# ProPrj_OPA4377__2025-12-12.net
KiCad netlist of a schematic drawn in EasyEDA Pro
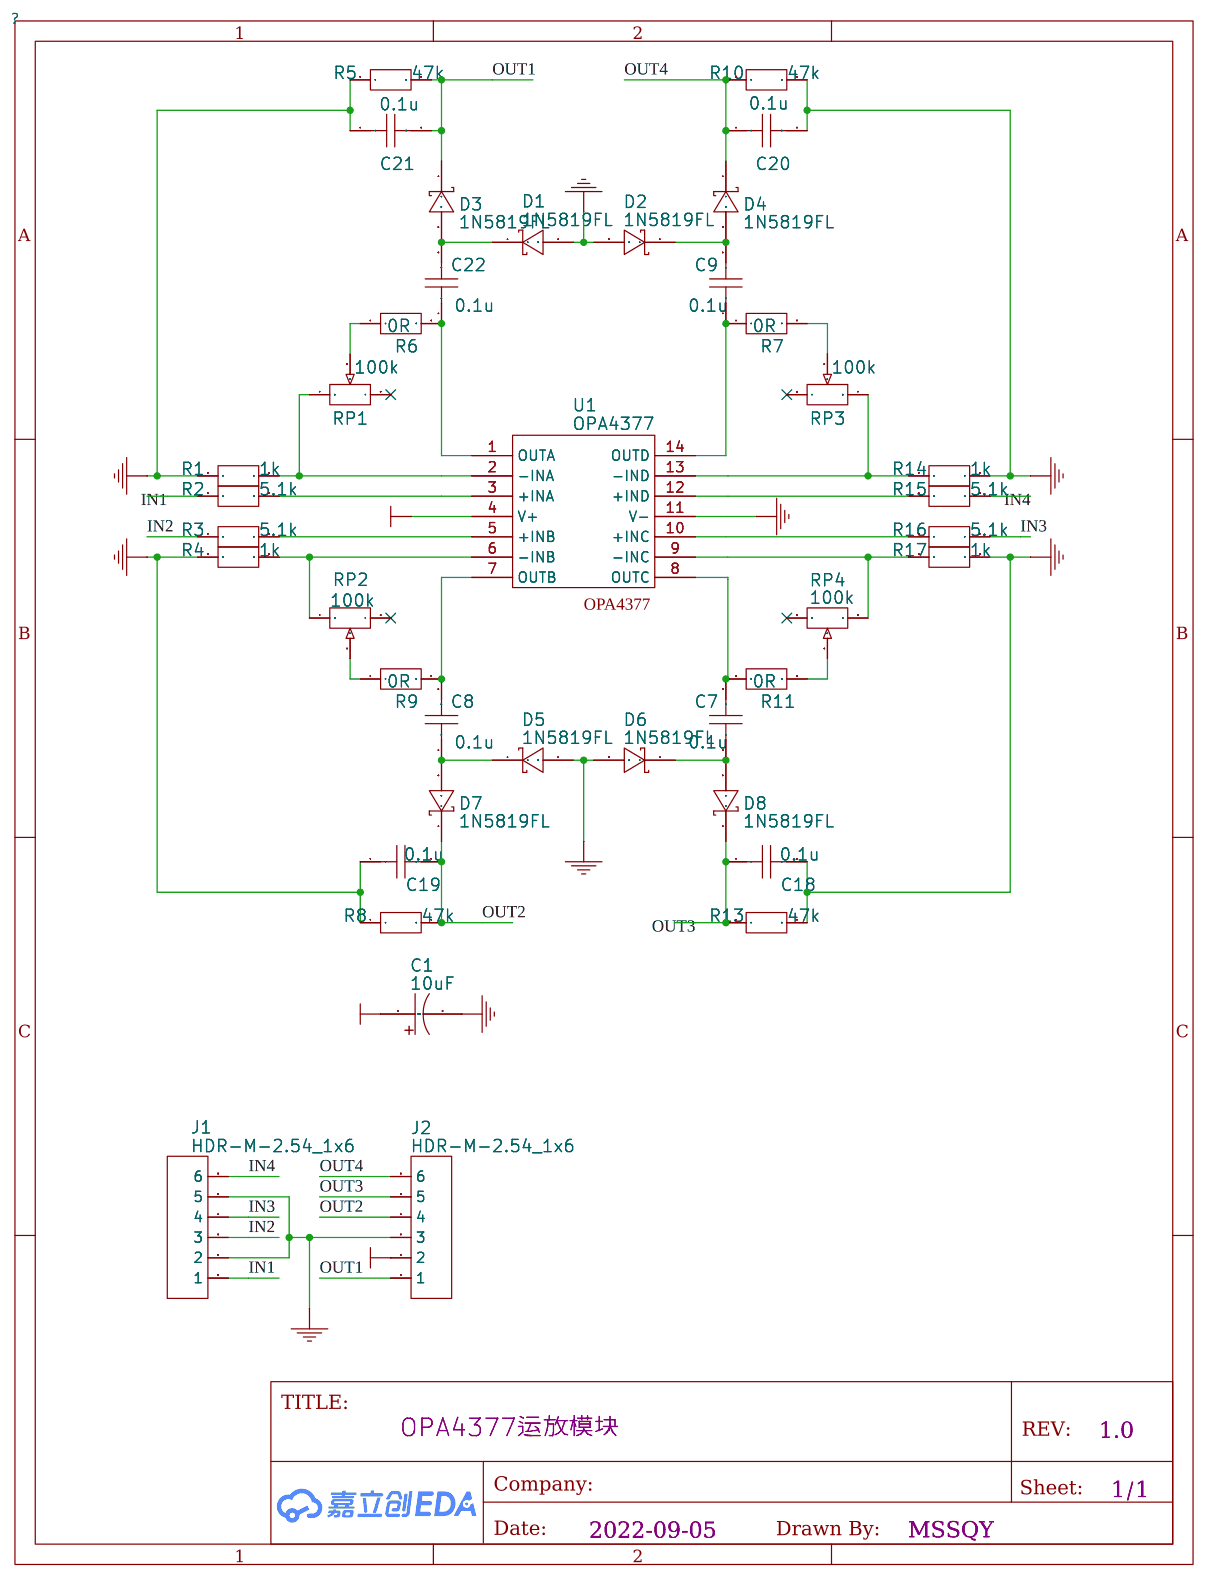
[diagram p0: schematic sheet]

(export (version "E")
  (design (tool "Eeschema 10.0.6"))
  (components
    (comp (ref "C1")
      (value "10uF")
      (fields (field (name "Manufacturer Part") "CA45-A-10V-10μF-K") (field (name "Manufacturer") "TORCH"))
      (libsource (lib "easyedapro") (part "10uF"))
    )
    (comp (ref "C7")
      (value "0.1u")
      (fields
        (field (name "Manufacturer Part") "MT18N101J500CT")
        (field (name "Manufacturer") "Huaxin S&amp;T")
      )
      (libsource (lib "easyedapro") (part "0.1u"))
    )
    (comp (ref "C8")
      (value "0.1u")
      (fields
        (field (name "Manufacturer Part") "MT18N101J500CT")
        (field (name "Manufacturer") "Huaxin S&amp;T")
      )
      (libsource (lib "easyedapro") (part "0.1u"))
    )
    (comp (ref "C9")
      (value "0.1u")
      (fields
        (field (name "Manufacturer Part") "MT18N101J500CT")
        (field (name "Manufacturer") "Huaxin S&amp;T")
      )
      (libsource (lib "easyedapro") (part "0.1u"))
    )
    (comp (ref "C18")
      (value "0.1u")
      (fields
        (field (name "Manufacturer Part") "MT18N101J500CT")
        (field (name "Manufacturer") "Huaxin S&amp;T")
      )
      (libsource (lib "easyedapro") (part "0.1u"))
    )
    (comp (ref "C19")
      (value "0.1u")
      (fields
        (field (name "Manufacturer Part") "MT18N101J500CT")
        (field (name "Manufacturer") "Huaxin S&amp;T")
      )
      (libsource (lib "easyedapro") (part "0.1u"))
    )
    (comp (ref "C20")
      (value "0.1u")
      (fields
        (field (name "Manufacturer Part") "MT18N101J500CT")
        (field (name "Manufacturer") "Huaxin S&amp;T")
      )
      (libsource (lib "easyedapro") (part "0.1u"))
    )
    (comp (ref "C21")
      (value "0.1u")
      (fields
        (field (name "Manufacturer Part") "MT18N101J500CT")
        (field (name "Manufacturer") "Huaxin S&amp;T")
      )
      (libsource (lib "easyedapro") (part "0.1u"))
    )
    (comp (ref "C22")
      (value "0.1u")
      (fields
        (field (name "Manufacturer Part") "MT18N101J500CT")
        (field (name "Manufacturer") "Huaxin S&amp;T")
      )
      (libsource (lib "easyedapro") (part "0.1u"))
    )
    (comp (ref "D1")
      (value "1N5819FL")
      (fields (field (name "Manufacturer") "KEXIN"))
      (libsource (lib "easyedapro") (part "1N5819FL"))
    )
    (comp (ref "D2")
      (value "1N5819FL")
      (fields (field (name "Manufacturer") "KEXIN"))
      (libsource (lib "easyedapro") (part "1N5819FL"))
    )
    (comp (ref "D3")
      (value "1N5819FL")
      (fields (field (name "Manufacturer") "KEXIN"))
      (libsource (lib "easyedapro") (part "1N5819FL"))
    )
    (comp (ref "D4")
      (value "1N5819FL")
      (fields (field (name "Manufacturer") "KEXIN"))
      (libsource (lib "easyedapro") (part "1N5819FL"))
    )
    (comp (ref "D5")
      (value "1N5819FL")
      (fields (field (name "Manufacturer") "KEXIN"))
      (libsource (lib "easyedapro") (part "1N5819FL"))
    )
    (comp (ref "D6")
      (value "1N5819FL")
      (fields (field (name "Manufacturer") "KEXIN"))
      (libsource (lib "easyedapro") (part "1N5819FL"))
    )
    (comp (ref "D7")
      (value "1N5819FL")
      (fields (field (name "Manufacturer") "KEXIN"))
      (libsource (lib "easyedapro") (part "1N5819FL"))
    )
    (comp (ref "D8")
      (value "1N5819FL")
      (fields (field (name "Manufacturer") "KEXIN"))
      (libsource (lib "easyedapro") (part "1N5819FL"))
    )
    (comp (ref "J1") (value "HDR-M-2.54_1x6") (libsource (lib "") (part "HDR-M-2.54_1x6_1")))
    (comp (ref "J2") (value "HDR-M-2.54_1x6") (libsource (lib "easyedapro") (part "HDR-M-2.54_1x6")))
    (comp (ref "R1")
      (value "1k")
      (fields (field (name "Manufacturer Part") "RT0603DRD071KL") (field (name "Manufacturer") "YAGEO"))
      (libsource (lib "easyedapro") (part "1k"))
    )
    (comp (ref "R2")
      (value "5.1k")
      (fields
        (field (name "Manufacturer Part") "RS-03K5101FT")
        (field (name "Manufacturer") "Guangdong Fenghua Advanced Tech")
      )
      (libsource (lib "easyedapro") (part "5.1k"))
    )
    (comp (ref "R3")
      (value "5.1k")
      (fields
        (field (name "Manufacturer Part") "RS-03K5101FT")
        (field (name "Manufacturer") "Guangdong Fenghua Advanced Tech")
      )
      (libsource (lib "easyedapro") (part "5.1k"))
    )
    (comp (ref "R4")
      (value "1k")
      (fields (field (name "Manufacturer Part") "RT0603DRD071KL") (field (name "Manufacturer") "YAGEO"))
      (libsource (lib "easyedapro") (part "1k"))
    )
    (comp (ref "R5")
      (value "47k")
      (fields (field (name "Manufacturer Part") "RS-03K473JT") (field (name "Manufacturer") "FH"))
      (libsource (lib "easyedapro") (part "0R"))
    )
    (comp (ref "R6")
      (value "0R")
      (fields (field (name "Manufacturer Part") "RS-03K473JT") (field (name "Manufacturer") "FH"))
      (libsource (lib "easyedapro") (part "0R"))
    )
    (comp (ref "R7")
      (value "0R")
      (fields (field (name "Manufacturer Part") "RS-03K473JT") (field (name "Manufacturer") "FH"))
      (libsource (lib "easyedapro") (part "0R"))
    )
    (comp (ref "R8")
      (value "47k")
      (fields (field (name "Manufacturer Part") "RS-03K473JT") (field (name "Manufacturer") "FH"))
      (libsource (lib "easyedapro") (part "0R"))
    )
    (comp (ref "R9")
      (value "0R")
      (fields (field (name "Manufacturer Part") "RS-03K473JT") (field (name "Manufacturer") "FH"))
      (libsource (lib "easyedapro") (part "0R"))
    )
    (comp (ref "R10")
      (value "47k")
      (fields (field (name "Manufacturer Part") "RS-03K473JT") (field (name "Manufacturer") "FH"))
      (libsource (lib "easyedapro") (part "0R"))
    )
    (comp (ref "R11")
      (value "0R")
      (fields (field (name "Manufacturer Part") "RS-03K473JT") (field (name "Manufacturer") "FH"))
      (libsource (lib "easyedapro") (part "0R"))
    )
    (comp (ref "R13")
      (value "47k")
      (fields (field (name "Manufacturer Part") "RS-03K473JT") (field (name "Manufacturer") "FH"))
      (libsource (lib "easyedapro") (part "0R"))
    )
    (comp (ref "R14")
      (value "1k")
      (fields (field (name "Manufacturer Part") "RT0603DRD071KL") (field (name "Manufacturer") "YAGEO"))
      (libsource (lib "easyedapro") (part "1k"))
    )
    (comp (ref "R15")
      (value "5.1k")
      (fields
        (field (name "Manufacturer Part") "RS-03K5101FT")
        (field (name "Manufacturer") "Guangdong Fenghua Advanced Tech")
      )
      (libsource (lib "easyedapro") (part "5.1k"))
    )
    (comp (ref "R16")
      (value "5.1k")
      (fields
        (field (name "Manufacturer Part") "RS-03K5101FT")
        (field (name "Manufacturer") "Guangdong Fenghua Advanced Tech")
      )
      (libsource (lib "easyedapro") (part "5.1k"))
    )
    (comp (ref "R17")
      (value "1k")
      (fields (field (name "Manufacturer Part") "RT0603DRD071KL") (field (name "Manufacturer") "YAGEO"))
      (libsource (lib "easyedapro") (part "1k"))
    )
    (comp (ref "RP1")
      (value "100k")
      (fields (field (name "Manufacturer") "Nidec Copal Elec"))
      (libsource (lib "") (part "100k_1"))
    )
    (comp (ref "RP2")
      (value "100k")
      (fields (field (name "Manufacturer") "Nidec Copal Elec"))
      (libsource (lib "easyedapro") (part "100k"))
    )
    (comp (ref "RP3")
      (value "100k")
      (fields (field (name "Manufacturer") "Nidec Copal Elec"))
      (libsource (lib "easyedapro") (part "100k"))
    )
    (comp (ref "RP4")
      (value "100k")
      (fields (field (name "Manufacturer") "Nidec Copal Elec"))
      (libsource (lib "") (part "100k_2"))
    )
    (comp (ref "U1")
      (value "OPA4377")
      (fields (field (name "Manufacturer") "OPA4377AIPWR"))
      (libsource (lib "easyedapro") (part "OPA4377"))
    )
  )
  (nets
    (net (code "1") (name "/IN1") (class "Default")
      (node (ref "J1") (pin "1") (pinfunction "1_1") (pintype "input"))
      (node (ref "R2") (pin "1") (pinfunction "1_1") (pintype "input"))
    )
    (net (code "2") (name "/IN2") (class "Default")
      (node (ref "J1") (pin "3") (pinfunction "3_3") (pintype "input"))
      (node (ref "R3") (pin "1") (pinfunction "1_1") (pintype "input"))
    )
    (net (code "3") (name "/IN3") (class "Default")
      (node (ref "J1") (pin "4") (pinfunction "4_4") (pintype "input"))
      (node (ref "R16") (pin "2") (pinfunction "2_2") (pintype "input"))
    )
    (net (code "4") (name "/IN4") (class "Default")
      (node (ref "J1") (pin "6") (pinfunction "6_6") (pintype "input"))
      (node (ref "R15") (pin "2") (pinfunction "2_2") (pintype "input"))
    )
    (net (code "5") (name "/OUT1") (class "Default")
      (node (ref "C21") (pin "2") (pinfunction "2_2") (pintype "input"))
      (node (ref "D3") (pin "1") (pinfunction "1_1") (pintype "input"))
      (node (ref "J2") (pin "1") (pinfunction "1_1") (pintype "input"))
      (node (ref "R5") (pin "2") (pinfunction "2_2") (pintype "input"))
    )
    (net (code "6") (name "/OUT2") (class "Default")
      (node (ref "C19") (pin "2") (pinfunction "2_2") (pintype "input"))
      (node (ref "D7") (pin "1") (pinfunction "1_1") (pintype "input"))
      (node (ref "J2") (pin "4") (pinfunction "4_4") (pintype "input"))
      (node (ref "R8") (pin "2") (pinfunction "2_2") (pintype "input"))
    )
    (net (code "7") (name "/OUT3") (class "Default")
      (node (ref "C18") (pin "1") (pinfunction "1_1") (pintype "input"))
      (node (ref "D8") (pin "1") (pinfunction "1_1") (pintype "input"))
      (node (ref "J2") (pin "5") (pinfunction "5_5") (pintype "input"))
      (node (ref "R13") (pin "1") (pinfunction "1_1") (pintype "input"))
    )
    (net (code "8") (name "/OUT4") (class "Default")
      (node (ref "C20") (pin "1") (pinfunction "1_1") (pintype "input"))
      (node (ref "D4") (pin "1") (pinfunction "1_1") (pintype "input"))
      (node (ref "J2") (pin "6") (pinfunction "6_6") (pintype "input"))
      (node (ref "R10") (pin "1") (pinfunction "1_1") (pintype "input"))
    )
    (net (code "9") (name "GND") (class "Default")
      (node (ref "C1") (pin "2") (pinfunction "2_2") (pintype "input"))
      (node (ref "C18") (pin "2") (pinfunction "2_2") (pintype "input"))
      (node (ref "C19") (pin "1") (pinfunction "1_1") (pintype "input"))
      (node (ref "C20") (pin "2") (pinfunction "2_2") (pintype "input"))
      (node (ref "C21") (pin "1") (pinfunction "1_1") (pintype "input"))
      (node (ref "D1") (pin "2") (pinfunction "2_2") (pintype "input"))
      (node (ref "D2") (pin "2") (pinfunction "2_2") (pintype "input"))
      (node (ref "D5") (pin "2") (pinfunction "2_2") (pintype "input"))
      (node (ref "D6") (pin "2") (pinfunction "2_2") (pintype "input"))
      (node (ref "J1") (pin "2") (pinfunction "2_2") (pintype "input"))
      (node (ref "J1") (pin "5") (pinfunction "5_5") (pintype "input"))
      (node (ref "J2") (pin "3") (pinfunction "3_3") (pintype "input"))
      (node (ref "R1") (pin "1") (pinfunction "1_1") (pintype "input"))
      (node (ref "R10") (pin "2") (pinfunction "2_2") (pintype "input"))
      (node (ref "R13") (pin "2") (pinfunction "2_2") (pintype "input"))
      (node (ref "R14") (pin "2") (pinfunction "2_2") (pintype "input"))
      (node (ref "R17") (pin "2") (pinfunction "2_2") (pintype "input"))
      (node (ref "R4") (pin "1") (pinfunction "1_1") (pintype "input"))
      (node (ref "R5") (pin "1") (pinfunction "1_1") (pintype "input"))
      (node (ref "R8") (pin "1") (pinfunction "1_1") (pintype "input"))
      (node (ref "U1") (pin "11") (pinfunction "V-_11") (pintype "input"))
    )
    (net (code "10") (name "Net-(C7-Pad1)") (class "Default")
      (node (ref "C7") (pin "1") (pinfunction "1_1") (pintype "input"))
      (node (ref "D6") (pin "1") (pinfunction "1_1") (pintype "input"))
      (node (ref "D8") (pin "2") (pinfunction "2_2") (pintype "input"))
    )
    (net (code "11") (name "Net-(C8-Pad1)") (class "Default")
      (node (ref "C8") (pin "1") (pinfunction "1_1") (pintype "input"))
      (node (ref "D5") (pin "1") (pinfunction "1_1") (pintype "input"))
      (node (ref "D7") (pin "2") (pinfunction "2_2") (pintype "input"))
    )
    (net (code "12") (name "Net-(C9-Pad2)") (class "Default")
      (node (ref "C9") (pin "2") (pinfunction "2_2") (pintype "input"))
      (node (ref "D2") (pin "1") (pinfunction "1_1") (pintype "input"))
      (node (ref "D4") (pin "2") (pinfunction "2_2") (pintype "input"))
    )
    (net (code "13") (name "Net-(C22-Pad2)") (class "Default")
      (node (ref "C22") (pin "2") (pinfunction "2_2") (pintype "input"))
      (node (ref "D1") (pin "1") (pinfunction "1_1") (pintype "input"))
      (node (ref "D3") (pin "2") (pinfunction "2_2") (pintype "input"))
    )
    (net (code "14") (name "Net-(R6-Pad1)") (class "Default")
      (node (ref "R6") (pin "1") (pinfunction "1_1") (pintype "input"))
      (node (ref "RP1") (pin "2") (pinfunction "2_2") (pintype "input"))
    )
    (net (code "15") (name "Net-(R7-Pad2)") (class "Default")
      (node (ref "R7") (pin "2") (pinfunction "2_2") (pintype "input"))
      (node (ref "RP3") (pin "2") (pinfunction "2_2") (pintype "input"))
    )
    (net (code "16") (name "Net-(R9-Pad1)") (class "Default")
      (node (ref "R9") (pin "1") (pinfunction "1_1") (pintype "input"))
      (node (ref "RP2") (pin "2") (pinfunction "2_2") (pintype "input"))
    )
    (net (code "17") (name "Net-(R11-Pad2)") (class "Default")
      (node (ref "R11") (pin "2") (pinfunction "2_2") (pintype "input"))
      (node (ref "RP4") (pin "2") (pinfunction "2_2") (pintype "input"))
    )
    (net (code "18") (name "Net-(RP1-3)") (class "Default")
      (node (ref "R1") (pin "2") (pinfunction "2_2") (pintype "input"))
      (node (ref "RP1") (pin "1") (pinfunction "3_1") (pintype "input"))
      (node (ref "U1") (pin "2") (pinfunction "-INA_2") (pintype "input"))
    )
    (net (code "19") (name "Net-(RP2-3)") (class "Default")
      (node (ref "R4") (pin "2") (pinfunction "2_2") (pintype "input"))
      (node (ref "RP2") (pin "1") (pinfunction "3_1") (pintype "input"))
      (node (ref "U1") (pin "6") (pinfunction "-INB_6") (pintype "input"))
    )
    (net (code "20") (name "Net-(RP3-3)") (class "Default")
      (node (ref "R14") (pin "1") (pinfunction "1_1") (pintype "input"))
      (node (ref "RP3") (pin "1") (pinfunction "3_1") (pintype "input"))
      (node (ref "U1") (pin "13") (pinfunction "-IND_13") (pintype "input"))
    )
    (net (code "21") (name "Net-(U1-+INA)") (class "Default")
      (node (ref "R2") (pin "2") (pinfunction "2_2") (pintype "input"))
      (node (ref "U1") (pin "3") (pinfunction "+INA_3") (pintype "input"))
    )
    (net (code "22") (name "Net-(U1-+INB)") (class "Default")
      (node (ref "R3") (pin "2") (pinfunction "2_2") (pintype "input"))
      (node (ref "U1") (pin "5") (pinfunction "+INB_5") (pintype "input"))
    )
    (net (code "23") (name "Net-(U1-+INC)") (class "Default")
      (node (ref "R16") (pin "1") (pinfunction "1_1") (pintype "input"))
      (node (ref "U1") (pin "10") (pinfunction "+INC_10") (pintype "input"))
    )
    (net (code "24") (name "Net-(U1-+IND)") (class "Default")
      (node (ref "R15") (pin "1") (pinfunction "1_1") (pintype "input"))
      (node (ref "U1") (pin "12") (pinfunction "+IND_12") (pintype "input"))
    )
    (net (code "25") (name "Net-(U1--INC)") (class "Default")
      (node (ref "R17") (pin "1") (pinfunction "1_1") (pintype "input"))
      (node (ref "RP4") (pin "1") (pinfunction "1_1") (pintype "input"))
      (node (ref "U1") (pin "9") (pinfunction "-INC_9") (pintype "input"))
    )
    (net (code "26") (name "Net-(U1-OUTA)") (class "Default")
      (node (ref "C22") (pin "1") (pinfunction "1_1") (pintype "input"))
      (node (ref "R6") (pin "2") (pinfunction "2_2") (pintype "input"))
      (node (ref "U1") (pin "1") (pinfunction "OUTA_1") (pintype "input"))
    )
    (net (code "27") (name "Net-(U1-OUTB)") (class "Default")
      (node (ref "C8") (pin "2") (pinfunction "2_2") (pintype "input"))
      (node (ref "R9") (pin "2") (pinfunction "2_2") (pintype "input"))
      (node (ref "U1") (pin "7") (pinfunction "OUTB_7") (pintype "input"))
    )
    (net (code "28") (name "Net-(U1-OUTC)") (class "Default")
      (node (ref "C7") (pin "2") (pinfunction "2_2") (pintype "input"))
      (node (ref "R11") (pin "1") (pinfunction "1_1") (pintype "input"))
      (node (ref "U1") (pin "8") (pinfunction "OUTC_8") (pintype "input"))
    )
    (net (code "29") (name "Net-(U1-OUTD)") (class "Default")
      (node (ref "C9") (pin "1") (pinfunction "1_1") (pintype "input"))
      (node (ref "R7") (pin "1") (pinfunction "1_1") (pintype "input"))
      (node (ref "U1") (pin "14") (pinfunction "OUTD_14") (pintype "input"))
    )
    (net (code "30") (name "VCC") (class "Default")
      (node (ref "C1") (pin "1") (pinfunction "1_1") (pintype "input"))
      (node (ref "J2") (pin "2") (pinfunction "2_2") (pintype "input"))
      (node (ref "U1") (pin "4") (pinfunction "V+_4") (pintype "input"))
    )
    (net (code "31") (name "unconnected-(RP1-1-Pad3)") (class "Default")
      (node (ref "RP1") (pin "3") (pinfunction "1_3") (pintype "input+no_connect"))
    )
    (net (code "32") (name "unconnected-(RP2-1-Pad3)") (class "Default")
      (node (ref "RP2") (pin "3") (pinfunction "1_3") (pintype "input+no_connect"))
    )
    (net (code "33") (name "unconnected-(RP3-1-Pad3)") (class "Default")
      (node (ref "RP3") (pin "3") (pinfunction "1_3") (pintype "input+no_connect"))
    )
    (net (code "34") (name "unconnected-(RP4-Pad3)") (class "Default")
      (node (ref "RP4") (pin "3") (pinfunction "3_3") (pintype "input+no_connect"))
    )
  )
)
